# CP2104-FO3-GM.net
KiCad netlist of a schematic drawn in Altium Designer
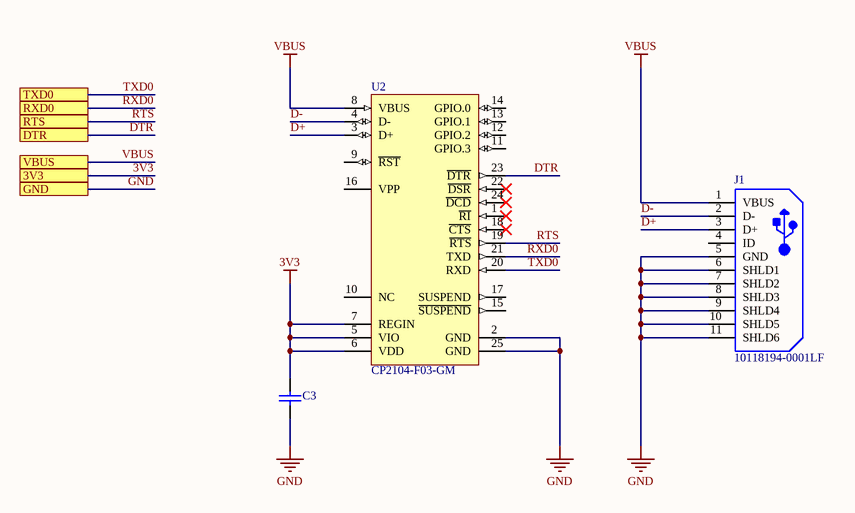
[diagram p0: CP2104-FO3-GM.SchDoc]

(export (version "E")
  (design (tool "Eeschema 10.0.6"))
  (components
    (comp (ref "C3")
      (value "C0805C106K4PACTU")
      (footprint "CAPC2013X140X50NL20T25")
      (description "10µF ±10% 16V Ceramic Capacitor X5R 0805 (2012 Metric)")
      (fields (field (name "PART NUMBER") "CL21A106KOQNNNG"))
      (libsource (lib "Altium Content Vault") (part "CAP"))
    )
    (comp (ref "J1")
      (value "10118194-0001LF")
      (footprint "FCI-10118194-0001LF-5_V")
      (description "Micro USB B Type Receptacle, 1.8 A, -55 to 85 degC, 5-Pin SMD, RoHS, Tape and Reel")
      (fields (field (name "MANUFACTURER") "Amphenol FCI"))
      (libsource (lib "Altium Content Vault") (part "USB-5-6SHLD"))
    )
    (comp (ref "U2")
      (value "CP2104-F03-GM")
      (footprint "SLAB-QFN-24-2675x2675TP_M")
      (fields (field (name "MANUFACTURER") "Silicon Labs"))
      (libsource (lib "Altium Content Vault") (part "SLAB-CP2104-QFN-24-25"))
    )
  )
  (nets
    (net (code "1") (name "/D+") (class "Default")
      (node (ref "J1") (pin "3") (pinfunction "D+_3") (pintype "passive"))
      (node (ref "U2") (pin "3") (pinfunction "D+_3") (pintype "bidirectional"))
    )
    (net (code "2") (name "/D-") (class "Default")
      (node (ref "J1") (pin "2") (pinfunction "D-_2") (pintype "passive"))
      (node (ref "U2") (pin "4") (pinfunction "D-_4") (pintype "bidirectional"))
    )
    (net (code "3") (name "/DTR") (class "Default")
      (node (ref "U2") (pin "23") (pinfunction "~{DTR}_23") (pintype "output"))
    )
    (net (code "4") (name "/RTS") (class "Default")
      (node (ref "U2") (pin "19") (pinfunction "~{RTS}_19") (pintype "output"))
    )
    (net (code "5") (name "/RXD0") (class "Default")
      (node (ref "U2") (pin "21") (pinfunction "TXD_21") (pintype "output"))
    )
    (net (code "6") (name "/TXD0") (class "Default")
      (node (ref "U2") (pin "20") (pinfunction "RXD_20") (pintype "input"))
    )
    (net (code "7") (name "3V3") (class "Default")
      (node (ref "C3") (pin "2") (pinfunction "2_2") (pintype "passive"))
      (node (ref "U2") (pin "5") (pinfunction "VIO_5") (pintype "power_in"))
      (node (ref "U2") (pin "6") (pinfunction "VDD_6") (pintype "power_in"))
      (node (ref "U2") (pin "7") (pinfunction "REGIN_7") (pintype "power_in"))
    )
    (net (code "8") (name "GND") (class "Default")
      (node (ref "C3") (pin "1") (pinfunction "1_1") (pintype "passive"))
      (node (ref "J1") (pin "10") (pinfunction "SHLD5_10") (pintype "passive"))
      (node (ref "J1") (pin "11") (pinfunction "SHLD6_11") (pintype "passive"))
      (node (ref "J1") (pin "5") (pinfunction "GND_5") (pintype "passive"))
      (node (ref "J1") (pin "6") (pinfunction "SHLD1_6") (pintype "passive"))
      (node (ref "J1") (pin "7") (pinfunction "SHLD2_7") (pintype "passive"))
      (node (ref "J1") (pin "8") (pinfunction "SHLD3_8") (pintype "passive"))
      (node (ref "J1") (pin "9") (pinfunction "SHLD4_9") (pintype "passive"))
      (node (ref "U2") (pin "2") (pinfunction "GND_2") (pintype "power_in"))
      (node (ref "U2") (pin "25") (pinfunction "GND_25") (pintype "power_in"))
    )
    (net (code "9") (name "VBUS") (class "Default")
      (node (ref "J1") (pin "1") (pinfunction "VBUS_1") (pintype "passive"))
      (node (ref "U2") (pin "8") (pinfunction "VBUS_8") (pintype "input"))
    )
    (net (code "10") (name "unconnected-(J1-ID-Pad4)") (class "Default")
      (node (ref "J1") (pin "4") (pinfunction "ID_4") (pintype "passive"))
    )
    (net (code "11") (name "unconnected-(U2-GPIO.0-Pad14)") (class "Default")
      (node (ref "U2") (pin "14") (pinfunction "GPIO.0_14") (pintype "bidirectional"))
    )
    (net (code "12") (name "unconnected-(U2-GPIO.1-Pad13)") (class "Default")
      (node (ref "U2") (pin "13") (pinfunction "GPIO.1_13") (pintype "bidirectional"))
    )
    (net (code "13") (name "unconnected-(U2-GPIO.2-Pad12)") (class "Default")
      (node (ref "U2") (pin "12") (pinfunction "GPIO.2_12") (pintype "bidirectional"))
    )
    (net (code "14") (name "unconnected-(U2-GPIO.3-Pad11)") (class "Default")
      (node (ref "U2") (pin "11") (pinfunction "GPIO.3_11") (pintype "bidirectional"))
    )
    (net (code "15") (name "unconnected-(U2-NC-Pad10)") (class "Default")
      (node (ref "U2") (pin "10") (pinfunction "NC_10") (pintype "passive"))
    )
    (net (code "16") (name "unconnected-(U2-SUSPEND-Pad17)") (class "Default")
      (node (ref "U2") (pin "17") (pinfunction "SUSPEND_17") (pintype "output"))
    )
    (net (code "17") (name "unconnected-(U2-VPP-Pad16)") (class "Default")
      (node (ref "U2") (pin "16") (pinfunction "VPP_16") (pintype "passive"))
    )
    (net (code "18") (name "unconnected-(U2-~{CTS}-Pad18)") (class "Default")
      (node (ref "U2") (pin "18") (pinfunction "~{CTS}_18") (pintype "input+no_connect"))
    )
    (net (code "19") (name "unconnected-(U2-~{DCD}-Pad24)") (class "Default")
      (node (ref "U2") (pin "24") (pinfunction "~{DCD}_24") (pintype "input+no_connect"))
    )
    (net (code "20") (name "unconnected-(U2-~{DSR}-Pad22)") (class "Default")
      (node (ref "U2") (pin "22") (pinfunction "~{DSR}_22") (pintype "input+no_connect"))
    )
    (net (code "21") (name "unconnected-(U2-~{RI}-Pad1)") (class "Default")
      (node (ref "U2") (pin "1") (pinfunction "~{RI}_1") (pintype "input+no_connect"))
    )
    (net (code "22") (name "unconnected-(U2-~{RST}-Pad9)") (class "Default")
      (node (ref "U2") (pin "9") (pinfunction "~{RST}_9") (pintype "bidirectional"))
    )
    (net (code "23") (name "unconnected-(U2-~{SUSPEND}-Pad15)") (class "Default")
      (node (ref "U2") (pin "15") (pinfunction "~{SUSPEND}_15") (pintype "output"))
    )
  )
)
